# H01R0_Backend.net
KiCad netlist of a schematic drawn in Altium Designer
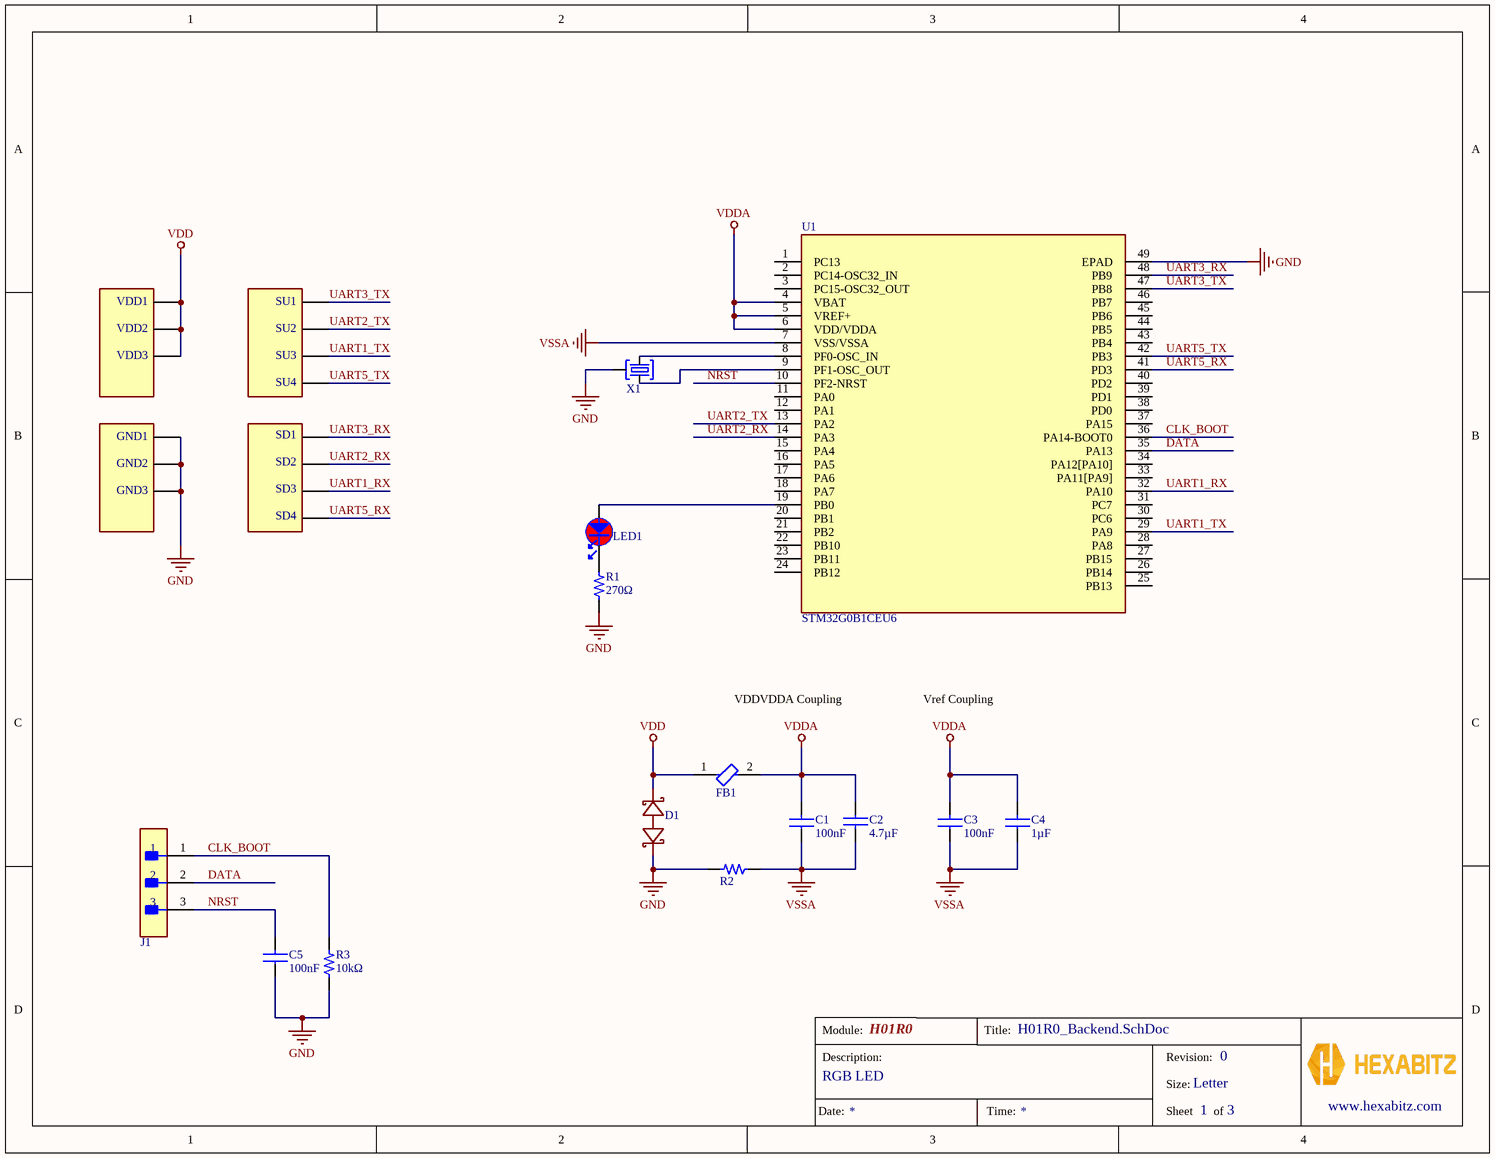
[diagram p0: H01R0_Backend.SchDoc]

(export (version "E")
  (design (tool "Eeschema 10.0.6"))
  (components
    (comp (ref "C1")
      (value "100nF")
      (footprint "C0603")
      (fields
        (field (name "MANUFACTURER") "Samsung Electro-Mechanics")
        (field (name "MANUFACTURER PART NUMBER") "CL10B104KA8NNNC")
        (field (name "TOLERANCE") "10%")
      )
      (libsource (lib "Hexabitz Altium Library") (part "generic Capacitor"))
    )
    (comp (ref "C2")
      (value "4.7µF")
      (footprint "C0805")
      (fields
        (field (name "MANUFACTURER") "Samsung Electro-Mechanics")
        (field (name "MANUFACTURER PART NUMBER") "CL21X475KAQNNNE")
        (field (name "TOLERANCE") "10%")
      )
      (libsource (lib "Hexabitz Altium Library") (part "generic Capacitor"))
    )
    (comp (ref "C3")
      (value "100nF")
      (footprint "C0603")
      (fields
        (field (name "MANUFACTURER") "Samsung Electro-Mechanics")
        (field (name "MANUFACTURER PART NUMBER") "CL10B104KA8NNNC")
        (field (name "TOLERANCE") "10%")
      )
      (libsource (lib "Hexabitz Altium Library") (part "generic Capacitor"))
    )
    (comp (ref "C4")
      (value "1µF")
      (footprint "C0805")
      (description "Ceramic Capacitor, Ceramic, 16V, 10% +Tol, 10% -Tol, X7R, 15% TC, 1uF, Surface Mount, 0805")
      (fields
        (field (name "MANUFACTURER") "Yageo Group")
        (field (name "MANUFACTURER PART NUMBER") "CC0805KKX7R7BB105")
      )
      (libsource (lib "Hexabitz Altium Library") (part "generic Capacitor"))
    )
    (comp (ref "C5")
      (value "100nF")
      (footprint "C0603")
      (fields
        (field (name "MANUFACTURER") "Samsung Electro-Mechanics")
        (field (name "MANUFACTURER PART NUMBER") "CL10B104KA8NNNC")
        (field (name "TOLERANCE") "10%")
      )
      (libsource (lib "Hexabitz Altium Library") (part "generic Capacitor"))
    )
    (comp (ref "D1")
      (value "CDSOD323-T03SC")
      (footprint "SOD2513X114N")
      (description "A 3V, 350W, bi-directional, standard capacitance, SOD323 pkg TVS Diode ¦ Bourns CDSOD323-T03SC")
      (fields (field (name "MANUFACTURER") "Bourns"))
      (libsource (lib "Hexabitz Altium Library") (part "CDSOD323-T03SC"))
    )
    (comp (ref "FB1")
      (value "MMZ1608Y300B")
      (footprint "FP-MMZ1608-0_8-MFG")
      (description "Ferrite Beads 0603 30ohms 1500mA Signal Line AEC-Q200")
      (fields
        (field (name "MANUFACTURER") "TDK")
        (field (name "MANUFACTURER PART NUMBER") "MMZ1608Y300BTD25")
      )
      (libsource (lib "Hexabitz Altium Library") (part "MMZ1608Y300B"))
    )
    (comp (ref "GND1")
      (value "HEXABIT_UART_PORT")
      (footprint "HEXABIT_POWER_PORT_D")
      (libsource (lib "hexabitz_connectors.Library") (part "HEXABIT_POWER_PORT_D"))
    )
    (comp (ref "GND2")
      (value "HEXABIT_UART_PORT")
      (footprint "HEXABIT_POWER_PORT_D")
      (libsource (lib "hexabitz_connectors.Library") (part "HEXABIT_POWER_PORT_D"))
    )
    (comp (ref "GND3")
      (value "HEXABIT_UART_PORT")
      (footprint "HEXABIT_POWER_PORT_D")
      (libsource (lib "hexabitz_connectors.Library") (part "HEXABIT_POWER_PORT_D"))
    )
    (comp (ref "J1")
      (value "TSW-103-14-G-S")
      (footprint "FP-TSW-103-14-G-S-MFG")
      (description "CONN HEADER VERT 3POS 2.54MM")
      (libsource (lib "Altium Content Vault") (part "cd3439d6ef35ae5d9b27ec4fdd3e828"))
    )
    (comp (ref "LED1")
      (value "VLMS1300-GS08")
      (footprint "FP-6_541-5092_01-4-MFG")
      (description "LED Uni-Color Super Red 639nm 2-Pin Chip 0603(1608Metric) T/R")
      (fields (field (name "MANUFACTURER") "Vishay Semiconductors"))
      (libsource (lib "Hexabitz Altium Library") (part "VLMS1300-GS08"))
    )
    (comp (ref "R1")
      (value "270Ω")
      (footprint "R0603")
      (description "Res Thick Film 0603 270 Ohm 5% 0.1W(1/10W) ±200ppm/C Pad SMD Automotive T/R")
      (fields
        (field (name "MANUFACTURER") "Panasonic")
        (field (name "MANUFACTURER PART NUMBER") "ERJ-3GEYJ271V")
      )
      (libsource (lib "") (part "generic Resistor_2"))
    )
    (comp (ref "R2")
      (value "Manufacturer Part Number")
      (footprint "R0603")
      (libsource (lib "Hexabitz Altium Library") (part "generic Resistor"))
    )
    (comp (ref "R3")
      (value "10kΩ")
      (footprint "R0603")
      (description "100mW Thick Film Resistors ±100ppm/℃ ±1% 10kΩ 0603 Chip Resistor - Surface Mount ROHS")
      (fields
        (field (name "MANUFACTURER") "Yageo Group")
        (field (name "MANUFACTURER PART NUMBER") "RC0603FR-0710KL")
      )
      (libsource (lib "") (part "generic Resistor_1"))
    )
    (comp (ref "SD1")
      (value "HEXABIT_UART_PORT")
      (footprint "HEXABIT_UART_PORT_D")
      (libsource (lib "hexabitz_connectors.Library") (part "HEXABIT_UART_PORT_D"))
    )
    (comp (ref "SD2")
      (value "HEXABIT_UART_PORT")
      (footprint "HEXABIT_UART_PORT_D")
      (libsource (lib "hexabitz_connectors.Library") (part "HEXABIT_UART_PORT_D"))
    )
    (comp (ref "SD3")
      (value "HEXABIT_UART_PORT")
      (footprint "HEXABIT_UART_PORT_D")
      (libsource (lib "hexabitz_connectors.Library") (part "HEXABIT_UART_PORT_D"))
    )
    (comp (ref "SD4")
      (value "HEXABIT_UART_PORT")
      (footprint "HEXABIT_UART_PORT_D")
      (libsource (lib "hexabitz_connectors.Library") (part "HEXABIT_UART_PORT_D"))
    )
    (comp (ref "SU1")
      (value "HEXABIT_UART_PORT")
      (footprint "HEXABIT_UART_PORT_U")
      (libsource (lib "hexabitz_connectors.Library") (part "HEXABIT_UART_PORT_U"))
    )
    (comp (ref "SU2")
      (value "HEXABIT_UART_PORT")
      (footprint "HEXABIT_UART_PORT_U")
      (libsource (lib "hexabitz_connectors.Library") (part "HEXABIT_UART_PORT_U"))
    )
    (comp (ref "SU3")
      (value "HEXABIT_UART_PORT")
      (footprint "HEXABIT_UART_PORT_U")
      (libsource (lib "hexabitz_connectors.Library") (part "HEXABIT_UART_PORT_U"))
    )
    (comp (ref "SU4")
      (value "HEXABIT_UART_PORT")
      (footprint "HEXABIT_UART_PORT_U")
      (libsource (lib "hexabitz_connectors.Library") (part "HEXABIT_UART_PORT_U"))
    )
    (comp (ref "U1")
      (value "STM32G0B1CEU6")
      (footprint "QFN50P700X700X65-49N-D")
      (description "MCU 32-bit ARM Cortex M0+ RISC 512KB Flash 1.8V/2.5V/3.3V 48-Pin UFQFPN EP Tray")
      (fields
        (field (name "MANUFACTURER") "STMicroelectronics")
        (field (name "MANUFACTURER PART NUMBER") "STM32G0B1CEU6")
      )
      (libsource (lib "Hexabitz Altium Library") (part "STM32G0B1CEU6"))
    )
    (comp (ref "VDD1")
      (value "HEXABIT_UART_PORT")
      (footprint "HEXABIT_POWER_PORT_U")
      (libsource (lib "hexabitz_connectors.Library") (part "HEXABIT_POWER_PORT_U"))
    )
    (comp (ref "VDD2")
      (value "HEXABIT_UART_PORT")
      (footprint "HEXABIT_POWER_PORT_U")
      (libsource (lib "hexabitz_connectors.Library") (part "HEXABIT_POWER_PORT_U"))
    )
    (comp (ref "VDD3")
      (value "HEXABIT_UART_PORT")
      (footprint "HEXABIT_POWER_PORT_U")
      (libsource (lib "hexabitz_connectors.Library") (part "HEXABIT_POWER_PORT_U"))
    )
    (comp (ref "X1")
      (value "CSTCE8M00G52Z-R0")
      (footprint "XTALL_CSTCE8M00G52")
      (description "Ceramic Resonator 8MHz ±0.5% (Tol) ±0.2% (Stability) 10pF 40Ohm 3-Pin CSMD T/R")
      (fields (field (name "MANUFACTURER") "Murata") (field (name "TOLERANCE") "0.5%"))
      (libsource (lib "Hexabitz Altium Library") (part "CSTCE8M00G52Z-R0"))
    )
  )
  (nets
    (net (code "1") (name "/CLK_BOOT") (class "Default")
      (node (ref "J1") (pin "1") (pinfunction "1_1") (pintype "passive"))
      (node (ref "R3") (pin "1") (pinfunction "1_1") (pintype "passive"))
      (node (ref "U1") (pin "36") (pinfunction "PA14-BOOT0_36") (pintype "passive"))
    )
    (net (code "2") (name "/DATA") (class "Default")
      (node (ref "J1") (pin "2") (pinfunction "2_2") (pintype "passive"))
      (node (ref "U1") (pin "35") (pinfunction "PA13_35") (pintype "passive"))
    )
    (net (code "3") (name "/NRST") (class "Default")
      (node (ref "C5") (pin "2") (pinfunction "2_2") (pintype "passive"))
      (node (ref "J1") (pin "3") (pinfunction "3_3") (pintype "passive"))
      (node (ref "U1") (pin "10") (pinfunction "PF2-NRST_10") (pintype "passive"))
    )
    (net (code "4") (name "/UART1_RX") (class "Default")
      (node (ref "SD3") (pin "UART_D") (pinfunction "UART_D_UART_D") (pintype "passive"))
      (node (ref "U1") (pin "32") (pinfunction "PA10_32") (pintype "passive"))
    )
    (net (code "5") (name "/UART1_TX") (class "Default")
      (node (ref "SU3") (pin "UART_U") (pinfunction "UART_U_UART_U") (pintype "passive"))
      (node (ref "U1") (pin "29") (pinfunction "PA9_29") (pintype "passive"))
    )
    (net (code "6") (name "/UART2_RX") (class "Default")
      (node (ref "SD2") (pin "UART_D") (pinfunction "UART_D_UART_D") (pintype "passive"))
      (node (ref "U1") (pin "14") (pinfunction "PA3_14") (pintype "passive"))
    )
    (net (code "7") (name "/UART2_TX") (class "Default")
      (node (ref "SU2") (pin "UART_U") (pinfunction "UART_U_UART_U") (pintype "passive"))
      (node (ref "U1") (pin "13") (pinfunction "PA2_13") (pintype "passive"))
    )
    (net (code "8") (name "/UART3_RX") (class "Default")
      (node (ref "SD1") (pin "UART_D") (pinfunction "UART_D_UART_D") (pintype "passive"))
      (node (ref "U1") (pin "48") (pinfunction "PB9_48") (pintype "passive"))
    )
    (net (code "9") (name "/UART3_TX") (class "Default")
      (node (ref "SU1") (pin "UART_U") (pinfunction "UART_U_UART_U") (pintype "passive"))
      (node (ref "U1") (pin "47") (pinfunction "PB8_47") (pintype "passive"))
    )
    (net (code "10") (name "/UART5_RX") (class "Default")
      (node (ref "SD4") (pin "UART_D") (pinfunction "UART_D_UART_D") (pintype "passive"))
      (node (ref "U1") (pin "41") (pinfunction "PD3_41") (pintype "passive"))
    )
    (net (code "11") (name "/UART5_TX") (class "Default")
      (node (ref "SU4") (pin "UART_U") (pinfunction "UART_U_UART_U") (pintype "passive"))
      (node (ref "U1") (pin "42") (pinfunction "PB3_42") (pintype "passive"))
    )
    (net (code "12") (name "GND") (class "Default")
      (node (ref "C5") (pin "1") (pinfunction "1_1") (pintype "passive"))
      (node (ref "D1") (pin "1") (pinfunction "A_1") (pintype "passive"))
      (node (ref "GND1") (pin "Pwr_D") (pinfunction "Pwr_D_Pwr_D") (pintype "passive"))
      (node (ref "GND2") (pin "Pwr_D") (pinfunction "Pwr_D_Pwr_D") (pintype "passive"))
      (node (ref "GND3") (pin "Pwr_D") (pinfunction "Pwr_D_Pwr_D") (pintype "passive"))
      (node (ref "R1") (pin "1") (pinfunction "1_1") (pintype "passive"))
      (node (ref "R2") (pin "1") (pinfunction "1_1") (pintype "passive"))
      (node (ref "R3") (pin "2") (pinfunction "2_2") (pintype "passive"))
      (node (ref "U1") (pin "49") (pinfunction "EPAD_49") (pintype "passive"))
      (node (ref "X1") (pin "P$2") (pinfunction "2_P$2") (pintype "passive"))
    )
    (net (code "13") (name "Net-(LED1-Pad1)") (class "Default")
      (node (ref "LED1") (pin "1") (pintype "passive"))
      (node (ref "R1") (pin "2") (pinfunction "2_2") (pintype "passive"))
    )
    (net (code "14") (name "Net-(U1-PB0)") (class "Default")
      (node (ref "LED1") (pin "2") (pintype "passive"))
      (node (ref "U1") (pin "19") (pinfunction "PB0_19") (pintype "passive"))
    )
    (net (code "15") (name "Net-(U1-PF0-OSC_IN)") (class "Default")
      (node (ref "U1") (pin "8") (pinfunction "PF0-OSC_IN_8") (pintype "passive"))
      (node (ref "X1") (pin "P$3") (pinfunction "3_P$3") (pintype "passive"))
    )
    (net (code "16") (name "Net-(U1-PF1-OSC_OUT)") (class "Default")
      (node (ref "U1") (pin "9") (pinfunction "PF1-OSC_OUT_9") (pintype "passive"))
      (node (ref "X1") (pin "P$1") (pinfunction "1_P$1") (pintype "passive"))
    )
    (net (code "17") (name "VDD") (class "Default")
      (node (ref "D1") (pin "2") (pinfunction "C_2") (pintype "passive"))
      (node (ref "FB1") (pin "1") (pinfunction "1_1") (pintype "passive"))
      (node (ref "VDD1") (pin "Pwr_U") (pinfunction "Pwr_U_Pwr_U") (pintype "passive"))
      (node (ref "VDD2") (pin "Pwr_U") (pinfunction "Pwr_U_Pwr_U") (pintype "passive"))
      (node (ref "VDD3") (pin "Pwr_U") (pinfunction "Pwr_U_Pwr_U") (pintype "passive"))
    )
    (net (code "18") (name "VDDA") (class "Default")
      (node (ref "C1") (pin "2") (pinfunction "2_2") (pintype "passive"))
      (node (ref "C2") (pin "1") (pinfunction "1_1") (pintype "passive"))
      (node (ref "C3") (pin "2") (pinfunction "2_2") (pintype "passive"))
      (node (ref "C4") (pin "2") (pinfunction "2_2") (pintype "passive"))
      (node (ref "FB1") (pin "2") (pinfunction "2_2") (pintype "passive"))
      (node (ref "U1") (pin "4") (pinfunction "VBAT_4") (pintype "passive"))
      (node (ref "U1") (pin "5") (pinfunction "VREF+_5") (pintype "passive"))
      (node (ref "U1") (pin "6") (pinfunction "VDD/VDDA_6") (pintype "passive"))
    )
    (net (code "19") (name "VSSA") (class "Default")
      (node (ref "C1") (pin "1") (pinfunction "1_1") (pintype "passive"))
      (node (ref "C2") (pin "2") (pinfunction "2_2") (pintype "passive"))
      (node (ref "C3") (pin "1") (pinfunction "1_1") (pintype "passive"))
      (node (ref "C4") (pin "1") (pinfunction "1_1") (pintype "passive"))
      (node (ref "R2") (pin "2") (pinfunction "2_2") (pintype "passive"))
      (node (ref "U1") (pin "7") (pinfunction "VSS/VSSA_7") (pintype "passive"))
    )
    (net (code "20") (name "unconnected-(U1-PA0-Pad11)") (class "Default")
      (node (ref "U1") (pin "11") (pinfunction "PA0_11") (pintype "passive"))
    )
    (net (code "21") (name "unconnected-(U1-PA1-Pad12)") (class "Default")
      (node (ref "U1") (pin "12") (pinfunction "PA1_12") (pintype "passive"))
    )
    (net (code "22") (name "unconnected-(U1-PA4-Pad15)") (class "Default")
      (node (ref "U1") (pin "15") (pinfunction "PA4_15") (pintype "passive"))
    )
    (net (code "23") (name "unconnected-(U1-PA5-Pad16)") (class "Default")
      (node (ref "U1") (pin "16") (pinfunction "PA5_16") (pintype "passive"))
    )
    (net (code "24") (name "unconnected-(U1-PA6-Pad17)") (class "Default")
      (node (ref "U1") (pin "17") (pinfunction "PA6_17") (pintype "passive"))
    )
    (net (code "25") (name "unconnected-(U1-PA7-Pad18)") (class "Default")
      (node (ref "U1") (pin "18") (pinfunction "PA7_18") (pintype "passive"))
    )
    (net (code "26") (name "unconnected-(U1-PA8-Pad28)") (class "Default")
      (node (ref "U1") (pin "28") (pinfunction "PA8_28") (pintype "passive"))
    )
    (net (code "27") (name "unconnected-(U1-PA11[PA9]-Pad33)") (class "Default")
      (node (ref "U1") (pin "33") (pinfunction "PA11[PA9]_33") (pintype "passive"))
    )
    (net (code "28") (name "unconnected-(U1-PA12[PA10]-Pad34)") (class "Default")
      (node (ref "U1") (pin "34") (pinfunction "PA12[PA10]_34") (pintype "passive"))
    )
    (net (code "29") (name "unconnected-(U1-PA15-Pad37)") (class "Default")
      (node (ref "U1") (pin "37") (pinfunction "PA15_37") (pintype "passive"))
    )
    (net (code "30") (name "unconnected-(U1-PB1-Pad20)") (class "Default")
      (node (ref "U1") (pin "20") (pinfunction "PB1_20") (pintype "passive"))
    )
    (net (code "31") (name "unconnected-(U1-PB2-Pad21)") (class "Default")
      (node (ref "U1") (pin "21") (pinfunction "PB2_21") (pintype "passive"))
    )
    (net (code "32") (name "unconnected-(U1-PB4-Pad43)") (class "Default")
      (node (ref "U1") (pin "43") (pinfunction "PB4_43") (pintype "passive"))
    )
    (net (code "33") (name "unconnected-(U1-PB5-Pad44)") (class "Default")
      (node (ref "U1") (pin "44") (pinfunction "PB5_44") (pintype "passive"))
    )
    (net (code "34") (name "unconnected-(U1-PB6-Pad45)") (class "Default")
      (node (ref "U1") (pin "45") (pinfunction "PB6_45") (pintype "passive"))
    )
    (net (code "35") (name "unconnected-(U1-PB7-Pad46)") (class "Default")
      (node (ref "U1") (pin "46") (pinfunction "PB7_46") (pintype "passive"))
    )
    (net (code "36") (name "unconnected-(U1-PB10-Pad22)") (class "Default")
      (node (ref "U1") (pin "22") (pinfunction "PB10_22") (pintype "passive"))
    )
    (net (code "37") (name "unconnected-(U1-PB11-Pad23)") (class "Default")
      (node (ref "U1") (pin "23") (pinfunction "PB11_23") (pintype "passive"))
    )
    (net (code "38") (name "unconnected-(U1-PB12-Pad24)") (class "Default")
      (node (ref "U1") (pin "24") (pinfunction "PB12_24") (pintype "passive"))
    )
    (net (code "39") (name "unconnected-(U1-PB13-Pad25)") (class "Default")
      (node (ref "U1") (pin "25") (pinfunction "PB13_25") (pintype "passive"))
    )
    (net (code "40") (name "unconnected-(U1-PB14-Pad26)") (class "Default")
      (node (ref "U1") (pin "26") (pinfunction "PB14_26") (pintype "passive"))
    )
    (net (code "41") (name "unconnected-(U1-PB15-Pad27)") (class "Default")
      (node (ref "U1") (pin "27") (pinfunction "PB15_27") (pintype "passive"))
    )
    (net (code "42") (name "unconnected-(U1-PC6-Pad30)") (class "Default")
      (node (ref "U1") (pin "30") (pinfunction "PC6_30") (pintype "passive"))
    )
    (net (code "43") (name "unconnected-(U1-PC7-Pad31)") (class "Default")
      (node (ref "U1") (pin "31") (pinfunction "PC7_31") (pintype "passive"))
    )
    (net (code "44") (name "unconnected-(U1-PC13-Pad1)") (class "Default")
      (node (ref "U1") (pin "1") (pinfunction "PC13_1") (pintype "passive"))
    )
    (net (code "45") (name "unconnected-(U1-PC14-OSC32_IN-Pad2)") (class "Default")
      (node (ref "U1") (pin "2") (pinfunction "PC14-OSC32_IN_2") (pintype "passive"))
    )
    (net (code "46") (name "unconnected-(U1-PC15-OSC32_OUT-Pad3)") (class "Default")
      (node (ref "U1") (pin "3") (pinfunction "PC15-OSC32_OUT_3") (pintype "passive"))
    )
    (net (code "47") (name "unconnected-(U1-PD0-Pad38)") (class "Default")
      (node (ref "U1") (pin "38") (pinfunction "PD0_38") (pintype "passive"))
    )
    (net (code "48") (name "unconnected-(U1-PD1-Pad39)") (class "Default")
      (node (ref "U1") (pin "39") (pinfunction "PD1_39") (pintype "passive"))
    )
    (net (code "49") (name "unconnected-(U1-PD2-Pad40)") (class "Default")
      (node (ref "U1") (pin "40") (pinfunction "PD2_40") (pintype "passive"))
    )
  )
)
